# BlueCom_Board.net
KiCad netlist of a schematic drawn in EAGLE
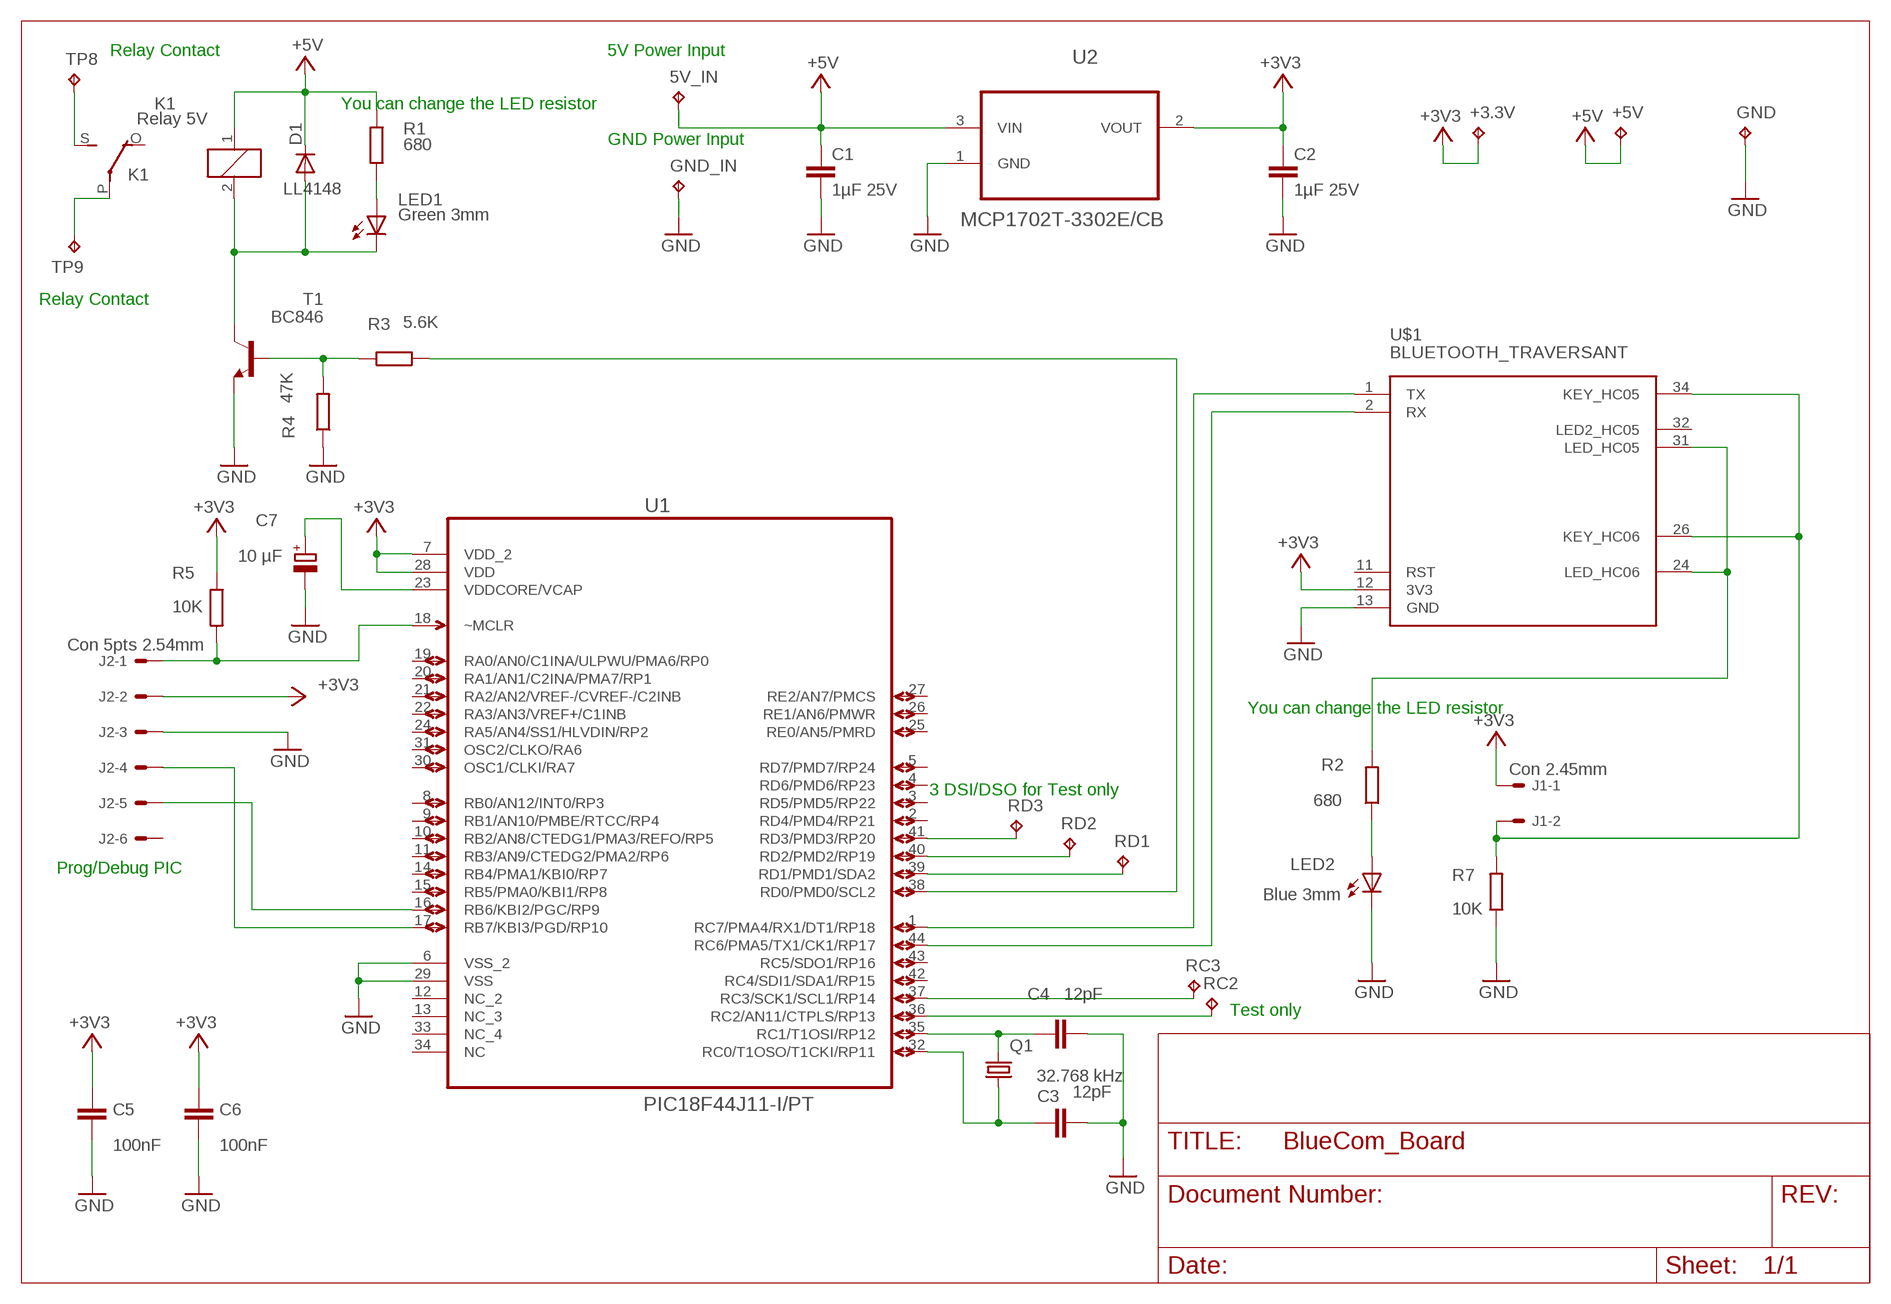
[diagram p0: schematic, sheet 1]

(export (version "E")
  (design (tool "Eeschema 10.0.6"))
  (components
    (comp (ref "+3.3V")
      (value "TPPAD1-13")
      (footprint "eagle-import:P1-13")
      (libsource (lib "eagle-import") (part "TPPAD1-13"))
    )
    (comp (ref "+5V")
      (value "TPPAD1-13")
      (footprint "eagle-import:P1-13")
      (libsource (lib "eagle-import") (part "TPPAD1-13"))
    )
    (comp (ref "5V_IN")
      (value "TPPAD1-13Y")
      (footprint "eagle-import:P1-13Y")
      (libsource (lib "eagle-import") (part "TPPAD1-13Y"))
    )
    (comp (ref "C1")
      (value "1µF 25V")
      (footprint "eagle-import:C0805")
      (libsource (lib "eagle-import") (part "C-EUC0805"))
    )
    (comp (ref "C2")
      (value "1µF 25V")
      (footprint "eagle-import:C0805")
      (libsource (lib "eagle-import") (part "C-EUC0805"))
    )
    (comp (ref "C3")
      (value "12pF")
      (footprint "eagle-import:C0805")
      (libsource (lib "eagle-import") (part "C-EUC0805"))
    )
    (comp (ref "C4")
      (value "12pF")
      (footprint "eagle-import:C0805")
      (libsource (lib "eagle-import") (part "C-EUC0805"))
    )
    (comp (ref "C5")
      (value "100nF")
      (footprint "eagle-import:C0805")
      (libsource (lib "eagle-import") (part "C-EUC0805"))
    )
    (comp (ref "C6")
      (value "100nF")
      (footprint "eagle-import:C0805")
      (libsource (lib "eagle-import") (part "C-EUC0805"))
    )
    (comp (ref "C7")
      (value "10 µF")
      (footprint "eagle-import:A_3216-18W")
      (libsource (lib "eagle-import") (part "CPOL-EUA/3216-18W"))
    )
    (comp (ref "D1")
      (value "LL4148")
      (footprint "eagle-import:SOD80C")
      (libsource (lib "eagle-import") (part "PMLL41SOD80C"))
    )
    (comp (ref "GND")
      (value "TPPAD1-13")
      (footprint "eagle-import:P1-13")
      (libsource (lib "eagle-import") (part "TPPAD1-13"))
    )
    (comp (ref "GND_IN")
      (value "TPPAD1-13Y")
      (footprint "eagle-import:P1-13Y")
      (libsource (lib "eagle-import") (part "TPPAD1-13Y"))
    )
    (comp (ref "J1")
      (value "Con 2.45mm")
      (footprint "eagle-import:6410-02")
      (fields (field (name "OC_FARNELL") "unknown"))
      (libsource (lib "eagle-import") (part "22-?-0227-2021"))
    )
    (comp (ref "J2")
      (value "Con 5pts 2.54mm")
      (footprint "eagle-import:6410-06")
      (libsource (lib "eagle-import") (part "22-?-0627-2061"))
    )
    (comp (ref "K1")
      (value "Relay 5V")
      (footprint "eagle-import:ZF112")
      (libsource (lib "eagle-import") (part "ZF112"))
    )
    (comp (ref "LED1")
      (value "Green 3mm")
      (footprint "eagle-import:LED3MM")
      (libsource (lib "eagle-import") (part "LED3MM"))
    )
    (comp (ref "LED2")
      (value "Blue 3mm")
      (footprint "eagle-import:LED3MM")
      (libsource (lib "eagle-import") (part "LED3MM"))
    )
    (comp (ref "Q1")
      (value "32.768 kHz")
      (footprint "eagle-import:TC26H")
      (libsource (lib "eagle-import") (part "CRYSTALTC26H"))
    )
    (comp (ref "R1")
      (value "680")
      (footprint "eagle-import:R0805")
      (libsource (lib "eagle-import") (part "R-EU_R0805"))
    )
    (comp (ref "R2")
      (value "680")
      (footprint "eagle-import:R0805")
      (libsource (lib "eagle-import") (part "R-EU_R0805"))
    )
    (comp (ref "R3")
      (value "5.6K")
      (footprint "eagle-import:R0805")
      (libsource (lib "eagle-import") (part "R-EU_R0805"))
    )
    (comp (ref "R4")
      (value "47K")
      (footprint "eagle-import:R0805")
      (libsource (lib "eagle-import") (part "R-EU_R0805"))
    )
    (comp (ref "R5")
      (value "10K")
      (footprint "eagle-import:R0805")
      (libsource (lib "eagle-import") (part "R-EU_R0805"))
    )
    (comp (ref "R7")
      (value "10K")
      (footprint "eagle-import:R0805")
      (libsource (lib "eagle-import") (part "R-EU_R0805"))
    )
    (comp (ref "RC2")
      (value "TPPAD1-13")
      (footprint "eagle-import:P1-13")
      (libsource (lib "eagle-import") (part "TPPAD1-13"))
    )
    (comp (ref "RC3")
      (value "TPPAD1-13")
      (footprint "eagle-import:P1-13")
      (libsource (lib "eagle-import") (part "TPPAD1-13"))
    )
    (comp (ref "RD1")
      (value "TPPAD1-13")
      (footprint "eagle-import:P1-13")
      (libsource (lib "eagle-import") (part "TPPAD1-13"))
    )
    (comp (ref "RD2")
      (value "TPPAD1-13")
      (footprint "eagle-import:P1-13")
      (libsource (lib "eagle-import") (part "TPPAD1-13"))
    )
    (comp (ref "RD3")
      (value "TPPAD1-13")
      (footprint "eagle-import:P1-13")
      (libsource (lib "eagle-import") (part "TPPAD1-13"))
    )
    (comp (ref "T1")
      (value "BC846")
      (footprint "eagle-import:SOT23")
      (libsource (lib "eagle-import") (part "BC846"))
    )
    (comp (ref "TP8")
      (value "TPPAD1-13Y")
      (footprint "eagle-import:P1-20Y")
      (libsource (lib "eagle-import") (part "TPPAD1-20Y"))
    )
    (comp (ref "TP9")
      (value "TPPAD1-13Y")
      (footprint "eagle-import:P1-20Y")
      (libsource (lib "eagle-import") (part "TPPAD1-20Y"))
    )
    (comp (ref "U$1")
      (value "BLUETOOTH_TRAVERSANT")
      (footprint "eagle-import:BLUETOOTH_TRAVERSANT")
      (libsource (lib "eagle-import") (part "BLUETOOTH_TRAVERSANT"))
    )
    (comp (ref "U1")
      (value "PIC18F44J11-I/PT")
      (footprint "eagle-import:QFP80P1200X1200X120-44N")
      (fields (field (name "MPN") "pic18f44j11-I/pt"))
      (libsource (lib "eagle-import") (part "PIC18F44J11-I/PT"))
    )
    (comp (ref "U2")
      (value "MCP1702T-3302E/CB")
      (footprint "eagle-import:SOT95P255X145-3N")
      (libsource (lib "eagle-import") (part "MCP1702T-3302E/CB"))
    )
  )
  (nets
    (net (code "1") (name "+3V3") (class "Default")
      (node (ref "+3.3V") (pin "TP") (pinfunction "TP_TP") (pintype "input"))
      (node (ref "C2") (pin "1") (pinfunction "1_1") (pintype "passive"))
      (node (ref "C5") (pin "1") (pinfunction "1_1") (pintype "passive"))
      (node (ref "C6") (pin "1") (pinfunction "1_1") (pintype "passive"))
      (node (ref "J1") (pin "1") (pinfunction "S_1") (pintype "passive"))
      (node (ref "J2") (pin "2") (pinfunction "S_2") (pintype "passive"))
      (node (ref "R5") (pin "1") (pinfunction "1_1") (pintype "passive"))
      (node (ref "U$1") (pin "12") (pinfunction "3V3_12") (pintype "bidirectional"))
      (node (ref "U1") (pin "28") (pinfunction "VDD_28") (pintype "power_in"))
      (node (ref "U1") (pin "7") (pinfunction "VDD_2_7") (pintype "power_in"))
      (node (ref "U2") (pin "2") (pinfunction "VOUT_2") (pintype "output"))
    )
    (net (code "2") (name "+5V") (class "Default")
      (node (ref "+5V") (pin "TP") (pinfunction "TP_TP") (pintype "input"))
      (node (ref "5V_IN") (pin "TP") (pinfunction "TP_TP") (pintype "input"))
      (node (ref "C1") (pin "1") (pinfunction "1_1") (pintype "passive"))
      (node (ref "D1") (pin "C") (pinfunction "C_C") (pintype "passive"))
      (node (ref "K1") (pin "1") (pinfunction "1_1") (pintype "passive"))
      (node (ref "R1") (pin "2") (pinfunction "2_2") (pintype "passive"))
      (node (ref "U2") (pin "3") (pinfunction "VIN_3") (pintype "input"))
    )
    (net (code "3") (name "GND") (class "Default")
      (node (ref "C1") (pin "2") (pinfunction "2_2") (pintype "passive"))
      (node (ref "C2") (pin "2") (pinfunction "2_2") (pintype "passive"))
      (node (ref "C3") (pin "2") (pinfunction "2_2") (pintype "passive"))
      (node (ref "C4") (pin "2") (pinfunction "2_2") (pintype "passive"))
      (node (ref "C5") (pin "2") (pinfunction "2_2") (pintype "passive"))
      (node (ref "C6") (pin "2") (pinfunction "2_2") (pintype "passive"))
      (node (ref "C7") (pin "-") (pinfunction "-_-") (pintype "passive"))
      (node (ref "GND") (pin "TP") (pinfunction "TP_TP") (pintype "input"))
      (node (ref "GND_IN") (pin "TP") (pinfunction "TP_TP") (pintype "input"))
      (node (ref "J2") (pin "3") (pinfunction "S_3") (pintype "passive"))
      (node (ref "LED2") (pin "K") (pinfunction "C_K") (pintype "passive"))
      (node (ref "R4") (pin "1") (pinfunction "1_1") (pintype "passive"))
      (node (ref "R7") (pin "1") (pinfunction "1_1") (pintype "passive"))
      (node (ref "T1") (pin "2") (pinfunction "E_2") (pintype "passive"))
      (node (ref "U$1") (pin "13") (pinfunction "GND_13") (pintype "bidirectional"))
      (node (ref "U1") (pin "29") (pinfunction "VSS_29") (pintype "power_in"))
      (node (ref "U1") (pin "6") (pinfunction "VSS_2_6") (pintype "power_in"))
      (node (ref "U2") (pin "1") (pinfunction "GND_1") (pintype "passive"))
    )
    (net (code "4") (name "Net-(J1B-S)") (class "Default")
      (node (ref "J1") (pin "2") (pinfunction "S_2") (pintype "passive"))
      (node (ref "R7") (pin "2") (pinfunction "2_2") (pintype "passive"))
      (node (ref "U$1") (pin "26") (pinfunction "KEY_HC06_26") (pintype "bidirectional"))
      (node (ref "U$1") (pin "34") (pinfunction "KEY_HC05_34") (pintype "bidirectional"))
    )
    (net (code "5") (name "Net-(J2A-S)") (class "Default")
      (node (ref "J2") (pin "1") (pinfunction "S_1") (pintype "passive"))
      (node (ref "R5") (pin "2") (pinfunction "2_2") (pintype "passive"))
      (node (ref "U1") (pin "18") (pinfunction "~{MCLR}_18") (pintype "input"))
    )
    (net (code "6") (name "Net-(J2D-S)") (class "Default")
      (node (ref "J2") (pin "4") (pinfunction "S_4") (pintype "passive"))
      (node (ref "U1") (pin "17") (pinfunction "RB7/KBI3/PGD/RP10_17") (pintype "bidirectional"))
    )
    (net (code "7") (name "Net-(J2E-S)") (class "Default")
      (node (ref "J2") (pin "5") (pinfunction "S_5") (pintype "passive"))
      (node (ref "U1") (pin "16") (pinfunction "RB6/KBI2/PGC/RP9_16") (pintype "bidirectional"))
    )
    (net (code "8") (name "Net-(K1-PadP)") (class "Default")
      (node (ref "K1") (pin "P") (pinfunction "P_P") (pintype "passive"))
      (node (ref "TP9") (pin "TP") (pinfunction "TP_TP") (pintype "input"))
    )
    (net (code "9") (name "Net-(K1-PadS)") (class "Default")
      (node (ref "K1") (pin "S") (pinfunction "S_S") (pintype "passive"))
      (node (ref "TP8") (pin "TP") (pinfunction "TP_TP") (pintype "input"))
    )
    (net (code "10") (name "Net-(LED1-C)") (class "Default")
      (node (ref "D1") (pin "A") (pinfunction "A_A") (pintype "passive"))
      (node (ref "K1") (pin "2") (pinfunction "2_2") (pintype "passive"))
      (node (ref "LED1") (pin "K") (pinfunction "C_K") (pintype "passive"))
      (node (ref "T1") (pin "3") (pinfunction "C_3") (pintype "passive"))
    )
    (net (code "11") (name "Net-(LED1-PadA)") (class "Default")
      (node (ref "LED1") (pin "A") (pinfunction "A_A") (pintype "passive"))
      (node (ref "R1") (pin "1") (pinfunction "1_1") (pintype "passive"))
    )
    (net (code "12") (name "Net-(LED2-PadA)") (class "Default")
      (node (ref "LED2") (pin "A") (pinfunction "A_A") (pintype "passive"))
      (node (ref "R2") (pin "1") (pinfunction "1_1") (pintype "passive"))
    )
    (net (code "13") (name "Net-(T1-B)") (class "Default")
      (node (ref "R3") (pin "1") (pinfunction "1_1") (pintype "passive"))
      (node (ref "R4") (pin "2") (pinfunction "2_2") (pintype "passive"))
      (node (ref "T1") (pin "1") (pinfunction "B_1") (pintype "passive"))
    )
    (net (code "14") (name "Net-(U$1-LED_HC05)") (class "Default")
      (node (ref "R2") (pin "2") (pinfunction "2_2") (pintype "passive"))
      (node (ref "U$1") (pin "24") (pinfunction "LED_HC06_24") (pintype "bidirectional"))
      (node (ref "U$1") (pin "31") (pinfunction "LED_HC05_31") (pintype "bidirectional"))
    )
    (net (code "15") (name "Net-(U$1-RX)") (class "Default")
      (node (ref "U$1") (pin "2") (pinfunction "RX_2") (pintype "bidirectional"))
      (node (ref "U1") (pin "44") (pinfunction "RC6/PMA5/TX1/CK1/RP17_44") (pintype "bidirectional"))
    )
    (net (code "16") (name "Net-(U$1-TX)") (class "Default")
      (node (ref "U$1") (pin "1") (pinfunction "TX_1") (pintype "bidirectional"))
      (node (ref "U1") (pin "1") (pinfunction "RC7/PMA4/RX1/DT1/RP18_1") (pintype "bidirectional"))
    )
    (net (code "17") (name "Net-(U1-RC0{slash}T1OSO{slash}T1CKI{slash}RP11)") (class "Default")
      (node (ref "C3") (pin "1") (pinfunction "1_1") (pintype "passive"))
      (node (ref "Q1") (pin "1") (pinfunction "1_1") (pintype "passive"))
      (node (ref "U1") (pin "32") (pinfunction "RC0/T1OSO/T1CKI/RP11_32") (pintype "bidirectional"))
    )
    (net (code "18") (name "Net-(U1-RC1{slash}T1OSI{slash}RP12)") (class "Default")
      (node (ref "C4") (pin "1") (pinfunction "1_1") (pintype "passive"))
      (node (ref "Q1") (pin "2") (pinfunction "2_2") (pintype "passive"))
      (node (ref "U1") (pin "35") (pinfunction "RC1/T1OSI/RP12_35") (pintype "bidirectional"))
    )
    (net (code "19") (name "Net-(U1-RC2{slash}AN11{slash}CTPLS{slash}RP13)") (class "Default")
      (node (ref "RC2") (pin "TP") (pinfunction "TP_TP") (pintype "input"))
      (node (ref "U1") (pin "36") (pinfunction "RC2/AN11/CTPLS/RP13_36") (pintype "bidirectional"))
    )
    (net (code "20") (name "Net-(U1-RC3{slash}SCK1{slash}SCL1{slash}RP14)") (class "Default")
      (node (ref "RC3") (pin "TP") (pinfunction "TP_TP") (pintype "input"))
      (node (ref "U1") (pin "37") (pinfunction "RC3/SCK1/SCL1/RP14_37") (pintype "bidirectional"))
    )
    (net (code "21") (name "Net-(U1-RD0{slash}PMD0{slash}SCL2)") (class "Default")
      (node (ref "R3") (pin "2") (pinfunction "2_2") (pintype "passive"))
      (node (ref "U1") (pin "38") (pinfunction "RD0/PMD0/SCL2_38") (pintype "bidirectional"))
    )
    (net (code "22") (name "Net-(U1-RD1{slash}PMD1{slash}SDA2)") (class "Default")
      (node (ref "RD1") (pin "TP") (pinfunction "TP_TP") (pintype "input"))
      (node (ref "U1") (pin "39") (pinfunction "RD1/PMD1/SDA2_39") (pintype "bidirectional"))
    )
    (net (code "23") (name "Net-(U1-RD2{slash}PMD2{slash}RP19)") (class "Default")
      (node (ref "RD2") (pin "TP") (pinfunction "TP_TP") (pintype "input"))
      (node (ref "U1") (pin "40") (pinfunction "RD2/PMD2/RP19_40") (pintype "bidirectional"))
    )
    (net (code "24") (name "Net-(U1-RD3{slash}PMD3{slash}RP20)") (class "Default")
      (node (ref "RD3") (pin "TP") (pinfunction "TP_TP") (pintype "input"))
      (node (ref "U1") (pin "41") (pinfunction "RD3/PMD3/RP20_41") (pintype "bidirectional"))
    )
    (net (code "25") (name "Net-(U1-VDDCORE{slash}VCAP)") (class "Default")
      (node (ref "C7") (pin "+") (pinfunction "+_+") (pintype "passive"))
      (node (ref "U1") (pin "23") (pinfunction "VDDCORE/VCAP_23") (pintype "bidirectional"))
    )
    (net (code "26") (name "unconnected-(J2F-S-Pad6)") (class "Default")
      (node (ref "J2") (pin "6") (pinfunction "S_6") (pintype "passive"))
    )
    (net (code "27") (name "unconnected-(K1-PadO)") (class "Default")
      (node (ref "K1") (pin "O") (pinfunction "O_O") (pintype "passive"))
    )
    (net (code "28") (name "unconnected-(U$1-LED2_HC05-Pad32)") (class "Default")
      (node (ref "U$1") (pin "32") (pinfunction "LED2_HC05_32") (pintype "bidirectional"))
    )
    (net (code "29") (name "unconnected-(U$1-RST-Pad11)") (class "Default")
      (node (ref "U$1") (pin "11") (pinfunction "RST_11") (pintype "bidirectional"))
    )
    (net (code "30") (name "unconnected-(U1-NC-Pad34)") (class "Default")
      (node (ref "U1") (pin "34") (pinfunction "NC_34") (pintype "no_connect"))
    )
    (net (code "31") (name "unconnected-(U1-NC_2-Pad12)") (class "Default")
      (node (ref "U1") (pin "12") (pinfunction "NC_2_12") (pintype "no_connect"))
    )
    (net (code "32") (name "unconnected-(U1-NC_3-Pad13)") (class "Default")
      (node (ref "U1") (pin "13") (pinfunction "NC_3_13") (pintype "no_connect"))
    )
    (net (code "33") (name "unconnected-(U1-NC_4-Pad33)") (class "Default")
      (node (ref "U1") (pin "33") (pinfunction "NC_4_33") (pintype "no_connect"))
    )
    (net (code "34") (name "unconnected-(U1-OSC1{slash}CLKI{slash}RA7-Pad30)") (class "Default")
      (node (ref "U1") (pin "30") (pinfunction "OSC1/CLKI/RA7_30") (pintype "bidirectional"))
    )
    (net (code "35") (name "unconnected-(U1-OSC2{slash}CLKO{slash}RA6-Pad31)") (class "Default")
      (node (ref "U1") (pin "31") (pinfunction "OSC2/CLKO/RA6_31") (pintype "bidirectional"))
    )
    (net (code "36") (name "unconnected-(U1-RA0{slash}AN0{slash}C1INA{slash}ULPWU{slash}PMA6{slash}RP0-Pad19)") (class "Default")
      (node (ref "U1") (pin "19") (pinfunction "RA0/AN0/C1INA/ULPWU/PMA6/RP0_19") (pintype "bidirectional"))
    )
    (net (code "37") (name "unconnected-(U1-RA1{slash}AN1{slash}C2INA{slash}PMA7{slash}RP1-Pad20)") (class "Default")
      (node (ref "U1") (pin "20") (pinfunction "RA1/AN1/C2INA/PMA7/RP1_20") (pintype "bidirectional"))
    )
    (net (code "38") (name "unconnected-(U1-RA2{slash}AN2{slash}VREF-{slash}CVREF-{slash}C2INB-Pad21)") (class "Default")
      (node (ref "U1") (pin "21") (pinfunction "RA2/AN2/VREF-/CVREF-/C2INB_21") (pintype "bidirectional"))
    )
    (net (code "39") (name "unconnected-(U1-RA3{slash}AN3{slash}VREF+{slash}C1INB-Pad22)") (class "Default")
      (node (ref "U1") (pin "22") (pinfunction "RA3/AN3/VREF+/C1INB_22") (pintype "bidirectional"))
    )
    (net (code "40") (name "unconnected-(U1-RA5{slash}AN4{slash}SS1{slash}HLVDIN{slash}RP2-Pad24)") (class "Default")
      (node (ref "U1") (pin "24") (pinfunction "RA5/AN4/SS1/HLVDIN/RP2_24") (pintype "bidirectional"))
    )
    (net (code "41") (name "unconnected-(U1-RB0{slash}AN12{slash}INT0{slash}RP3-Pad8)") (class "Default")
      (node (ref "U1") (pin "8") (pinfunction "RB0/AN12/INT0/RP3_8") (pintype "bidirectional"))
    )
    (net (code "42") (name "unconnected-(U1-RB1{slash}AN10{slash}PMBE{slash}RTCC{slash}RP4-Pad9)") (class "Default")
      (node (ref "U1") (pin "9") (pinfunction "RB1/AN10/PMBE/RTCC/RP4_9") (pintype "bidirectional"))
    )
    (net (code "43") (name "unconnected-(U1-RB2{slash}AN8{slash}CTEDG1{slash}PMA3{slash}REFO{slash}RP5-Pad10)") (class "Default")
      (node (ref "U1") (pin "10") (pinfunction "RB2/AN8/CTEDG1/PMA3/REFO/RP5_10") (pintype "bidirectional"))
    )
    (net (code "44") (name "unconnected-(U1-RB3{slash}AN9{slash}CTEDG2{slash}PMA2{slash}RP6-Pad11)") (class "Default")
      (node (ref "U1") (pin "11") (pinfunction "RB3/AN9/CTEDG2/PMA2/RP6_11") (pintype "bidirectional"))
    )
    (net (code "45") (name "unconnected-(U1-RB4{slash}PMA1{slash}KBI0{slash}RP7-Pad14)") (class "Default")
      (node (ref "U1") (pin "14") (pinfunction "RB4/PMA1/KBI0/RP7_14") (pintype "bidirectional"))
    )
    (net (code "46") (name "unconnected-(U1-RB5{slash}PMA0{slash}KBI1{slash}RP8-Pad15)") (class "Default")
      (node (ref "U1") (pin "15") (pinfunction "RB5/PMA0/KBI1/RP8_15") (pintype "bidirectional"))
    )
    (net (code "47") (name "unconnected-(U1-RC4{slash}SDI1{slash}SDA1{slash}RP15-Pad42)") (class "Default")
      (node (ref "U1") (pin "42") (pinfunction "RC4/SDI1/SDA1/RP15_42") (pintype "bidirectional"))
    )
    (net (code "48") (name "unconnected-(U1-RC5{slash}SDO1{slash}RP16-Pad43)") (class "Default")
      (node (ref "U1") (pin "43") (pinfunction "RC5/SDO1/RP16_43") (pintype "bidirectional"))
    )
    (net (code "49") (name "unconnected-(U1-RD4{slash}PMD4{slash}RP21-Pad2)") (class "Default")
      (node (ref "U1") (pin "2") (pinfunction "RD4/PMD4/RP21_2") (pintype "bidirectional"))
    )
    (net (code "50") (name "unconnected-(U1-RD5{slash}PMD5{slash}RP22-Pad3)") (class "Default")
      (node (ref "U1") (pin "3") (pinfunction "RD5/PMD5/RP22_3") (pintype "bidirectional"))
    )
    (net (code "51") (name "unconnected-(U1-RD6{slash}PMD6{slash}RP23-Pad4)") (class "Default")
      (node (ref "U1") (pin "4") (pinfunction "RD6/PMD6/RP23_4") (pintype "bidirectional"))
    )
    (net (code "52") (name "unconnected-(U1-RD7{slash}PMD7{slash}RP24-Pad5)") (class "Default")
      (node (ref "U1") (pin "5") (pinfunction "RD7/PMD7/RP24_5") (pintype "bidirectional"))
    )
    (net (code "53") (name "unconnected-(U1-RE0{slash}AN5{slash}PMRD-Pad25)") (class "Default")
      (node (ref "U1") (pin "25") (pinfunction "RE0/AN5/PMRD_25") (pintype "bidirectional"))
    )
    (net (code "54") (name "unconnected-(U1-RE1{slash}AN6{slash}PMWR-Pad26)") (class "Default")
      (node (ref "U1") (pin "26") (pinfunction "RE1/AN6/PMWR_26") (pintype "bidirectional"))
    )
    (net (code "55") (name "unconnected-(U1-RE2{slash}AN7{slash}PMCS-Pad27)") (class "Default")
      (node (ref "U1") (pin "27") (pinfunction "RE2/AN7/PMCS_27") (pintype "bidirectional"))
    )
  )
)
